# single_in_array_wth_para.net
KiCad netlist of a schematic drawn in EAGLE
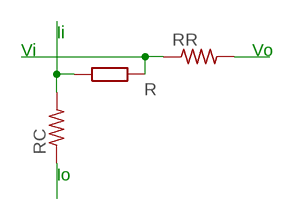
[diagram p0: schematic, sheet 1]

(export (version "E")
  (design (tool "Eeschema 10.0.6"))
  (components
    (comp (ref "R")
      (value "R-EU_0204/2V")
      (footprint "eagle-import:0204V")
      (libsource (lib "eagle-import") (part "R-EU_0204/2V"))
    )
    (comp (ref "RC")
      (value "R-US_0204/2V")
      (footprint "eagle-import:0204V")
      (libsource (lib "eagle-import") (part "R-US_0204/2V"))
    )
    (comp (ref "RR")
      (value "R-US_0204/2V")
      (footprint "eagle-import:0204V")
      (libsource (lib "eagle-import") (part "R-US_0204/2V"))
    )
  )
  (nets
    (net (code "1") (name "Net-(R-Pad1)") (class "Default")
      (node (ref "R") (pin "1") (pinfunction "1_1") (pintype "passive"))
      (node (ref "RC") (pin "2") (pinfunction "2_2") (pintype "passive"))
    )
    (net (code "2") (name "Net-(R-Pad2)") (class "Default")
      (node (ref "R") (pin "2") (pinfunction "2_2") (pintype "passive"))
      (node (ref "RR") (pin "1") (pinfunction "1_1") (pintype "passive"))
    )
    (net (code "3") (name "unconnected-(RC-Pad1)") (class "Default")
      (node (ref "RC") (pin "1") (pinfunction "1_1") (pintype "passive"))
    )
    (net (code "4") (name "unconnected-(RR-Pad2)") (class "Default")
      (node (ref "RR") (pin "2") (pinfunction "2_2") (pintype "passive"))
    )
  )
)
